# hydroponics_schema.net
KiCad netlist of a schematic drawn in EAGLE
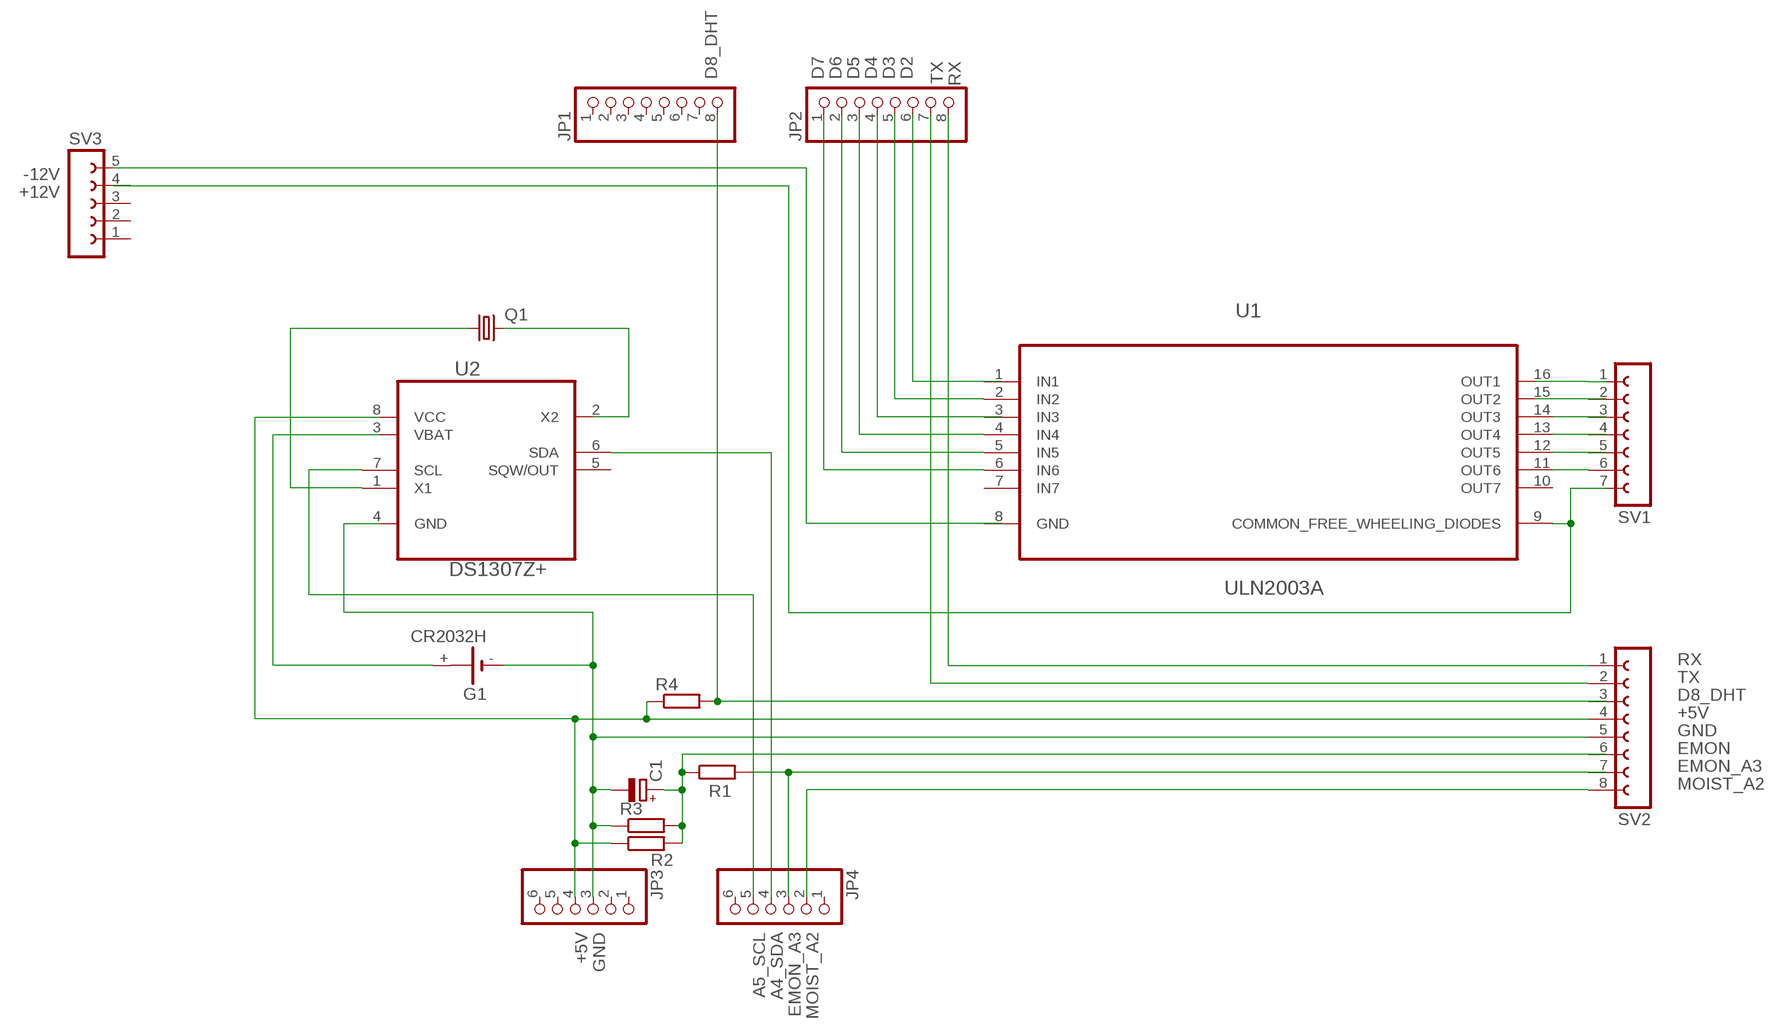
[diagram p0: schematic, sheet 1]

(export (version "E")
  (design (tool "Eeschema 10.0.6"))
  (components
    (comp (ref "C1")
      (value "CPOL-EUE2.5-6")
      (footprint "eagle-import:E2,5-6")
      (libsource (lib "eagle-import") (part "CPOL-EUE2.5-6"))
    )
    (comp (ref "G1")
      (value "CR2032H")
      (footprint "eagle-import:CR2032H")
      (libsource (lib "eagle-import") (part "CR2032H"))
    )
    (comp (ref "JP1")
      (value "PINHD-1X8/90")
      (footprint "eagle-import:1X08_90")
      (libsource (lib "eagle-import") (part "PINHD-1X8/90"))
    )
    (comp (ref "JP2")
      (value "PINHD-1X8/90")
      (footprint "eagle-import:1X08_90")
      (libsource (lib "eagle-import") (part "PINHD-1X8/90"))
    )
    (comp (ref "JP3")
      (value "PINHD-1X6/90")
      (footprint "eagle-import:1X06_90")
      (libsource (lib "eagle-import") (part "PINHD-1X6/90"))
    )
    (comp (ref "JP4")
      (value "PINHD-1X6/90")
      (footprint "eagle-import:1X06_90")
      (libsource (lib "eagle-import") (part "PINHD-1X6/90"))
    )
    (comp (ref "Q1")
      (value "CRYSTALTC38H")
      (footprint "eagle-import:TC38H")
      (libsource (lib "eagle-import") (part "CRYSTALTC38H"))
    )
    (comp (ref "R1")
      (value "R-EU_0207/10")
      (footprint "eagle-import:0207_10")
      (libsource (lib "eagle-import") (part "R-EU_0207/10"))
    )
    (comp (ref "R2")
      (value "R-EU_0207/10")
      (footprint "eagle-import:0207_10")
      (libsource (lib "eagle-import") (part "R-EU_0207/10"))
    )
    (comp (ref "R3")
      (value "R-EU_0207/10")
      (footprint "eagle-import:0207_10")
      (libsource (lib "eagle-import") (part "R-EU_0207/10"))
    )
    (comp (ref "R4")
      (value "R-EU_0207/10")
      (footprint "eagle-import:0207_10")
      (libsource (lib "eagle-import") (part "R-EU_0207/10"))
    )
    (comp (ref "SV1")
      (value "FE07-1")
      (footprint "eagle-import:FE07")
      (libsource (lib "eagle-import") (part "FE07-1"))
    )
    (comp (ref "SV2")
      (value "FE08-1")
      (footprint "eagle-import:FE08")
      (libsource (lib "eagle-import") (part "FE08-1"))
    )
    (comp (ref "SV3")
      (value "FE05-1")
      (footprint "eagle-import:FE05-1")
      (libsource (lib "eagle-import") (part "FE05-1"))
    )
    (comp (ref "U1")
      (value "ULN2003A")
      (footprint "eagle-import:DIP254P762X508-16")
      (fields (field (name "MF") "Arrow Electronics"))
      (libsource (lib "eagle-import") (part "ULN2003A"))
    )
    (comp (ref "U2")
      (value "DS1307Z+")
      (footprint "eagle-import:SOIC127P600X175-8N")
      (fields (field (name "MF") "DALLAS SEMICONDUCTOR"))
      (libsource (lib "eagle-import") (part "DS1307Z+"))
    )
  )
  (nets
    (net (code "1") (name "/+5V") (class "Default")
      (node (ref "JP3") (pin "4") (pinfunction "4_4") (pintype "passive"))
      (node (ref "R2") (pin "1") (pinfunction "1_1") (pintype "passive"))
      (node (ref "R4") (pin "1") (pinfunction "1_1") (pintype "passive"))
      (node (ref "SV2") (pin "4") (pinfunction "4_4") (pintype "passive"))
    )
    (net (code "2") (name "/+12V") (class "Default")
      (node (ref "U1") (pin "9") (pinfunction "COMMON_FREE_WHEELING_DIODES_9") (pintype "passive"))
    )
    (net (code "4") (name "/A4_SDA") (class "Default")
      (node (ref "JP4") (pin "4") (pinfunction "4_4") (pintype "passive"))
      (node (ref "U2") (pin "6") (pinfunction "SDA_6") (pintype "bidirectional"))
    )
    (net (code "5") (name "/A5_SCL") (class "Default")
      (node (ref "JP4") (pin "5") (pinfunction "5_5") (pintype "passive"))
      (node (ref "U2") (pin "7") (pinfunction "SCL_7") (pintype "input"))
    )
    (net (code "6") (name "/D2") (class "Default")
      (node (ref "JP2") (pin "6") (pinfunction "6_6") (pintype "passive"))
    )
    (net (code "7") (name "/D3") (class "Default")
      (node (ref "JP2") (pin "5") (pinfunction "5_5") (pintype "passive"))
      (node (ref "U1") (pin "2") (pinfunction "IN2_2") (pintype "input"))
    )
    (net (code "8") (name "/D4") (class "Default")
      (node (ref "JP2") (pin "4") (pinfunction "4_4") (pintype "passive"))
    )
    (net (code "9") (name "/D5") (class "Default")
      (node (ref "JP2") (pin "3") (pinfunction "3_3") (pintype "passive"))
      (node (ref "U1") (pin "4") (pinfunction "IN4_4") (pintype "input"))
    )
    (net (code "10") (name "/D6") (class "Default")
      (node (ref "JP2") (pin "2") (pinfunction "2_2") (pintype "passive"))
      (node (ref "U1") (pin "5") (pinfunction "IN5_5") (pintype "input"))
    )
    (net (code "11") (name "/D7") (class "Default")
      (node (ref "JP2") (pin "1") (pinfunction "1_1") (pintype "passive"))
      (node (ref "U1") (pin "6") (pinfunction "IN6_6") (pintype "input"))
    )
    (net (code "12") (name "/D8_DHT") (class "Default")
      (node (ref "JP1") (pin "8") (pinfunction "8_8") (pintype "passive"))
      (node (ref "R4") (pin "2") (pinfunction "2_2") (pintype "passive"))
    )
    (net (code "13") (name "/EMON") (class "Default")
      (node (ref "C1") (pin "+") (pinfunction "+_+") (pintype "passive"))
      (node (ref "R1") (pin "1") (pinfunction "1_1") (pintype "passive"))
      (node (ref "R2") (pin "2") (pinfunction "2_2") (pintype "passive"))
      (node (ref "R3") (pin "2") (pinfunction "2_2") (pintype "passive"))
    )
    (net (code "14") (name "/EMON_A3") (class "Default")
      (node (ref "JP4") (pin "3") (pinfunction "3_3") (pintype "passive"))
      (node (ref "R1") (pin "2") (pinfunction "2_2") (pintype "passive"))
    )
    (net (code "15") (name "/GND") (class "Default")
      (node (ref "C1") (pin "-") (pinfunction "-_-") (pintype "passive"))
      (node (ref "G1") (pin "-") (pinfunction "-_-") (pintype "passive"))
      (node (ref "JP3") (pin "3") (pinfunction "3_3") (pintype "passive"))
      (node (ref "R3") (pin "1") (pinfunction "1_1") (pintype "passive"))
      (node (ref "SV2") (pin "5") (pinfunction "5_5") (pintype "passive"))
    )
    (net (code "16") (name "/MOIST_A2") (class "Default")
      (node (ref "JP4") (pin "2") (pinfunction "2_2") (pintype "passive"))
      (node (ref "SV2") (pin "8") (pinfunction "8_8") (pintype "passive"))
    )
    (net (code "17") (name "/RX") (class "Default")
      (node (ref "JP2") (pin "8") (pinfunction "8_8") (pintype "passive"))
      (node (ref "SV2") (pin "1") (pinfunction "1_1") (pintype "passive"))
    )
    (net (code "18") (name "/TX") (class "Default")
      (node (ref "JP2") (pin "7") (pinfunction "7_7") (pintype "passive"))
      (node (ref "SV2") (pin "2") (pinfunction "2_2") (pintype "passive"))
    )
    (net (code "19") (name "/VCC") (class "Default")
      (node (ref "U2") (pin "8") (pinfunction "VCC_8") (pintype "power_in"))
    )
    (net (code "20") (name "Net-(U1-OUT6)") (class "Default")
      (node (ref "SV1") (pin "6") (pinfunction "6_6") (pintype "passive"))
      (node (ref "U1") (pin "11") (pinfunction "OUT6_11") (pintype "output"))
    )
    (net (code "21") (name "Net-(U2-X1)") (class "Default")
      (node (ref "Q1") (pin "1") (pinfunction "1_1") (pintype "passive"))
      (node (ref "U2") (pin "1") (pinfunction "X1_1") (pintype "input"))
    )
    (net (code "22") (name "unconnected-(G1-+-Pad+@1)") (class "Default")
      (node (ref "G1") (pin "+@1") (pinfunction "+_+@1") (pintype "passive"))
    )
    (net (code "23") (name "unconnected-(G1-Pad+)") (class "Default")
      (node (ref "G1") (pin "+") (pinfunction "+_+") (pintype "passive"))
    )
    (net (code "24") (name "unconnected-(JP1-Pad1)") (class "Default")
      (node (ref "JP1") (pin "1") (pinfunction "1_1") (pintype "passive"))
    )
    (net (code "25") (name "unconnected-(JP1-Pad2)") (class "Default")
      (node (ref "JP1") (pin "2") (pinfunction "2_2") (pintype "passive"))
    )
    (net (code "26") (name "unconnected-(JP1-Pad3)") (class "Default")
      (node (ref "JP1") (pin "3") (pinfunction "3_3") (pintype "passive"))
    )
    (net (code "27") (name "unconnected-(JP1-Pad4)") (class "Default")
      (node (ref "JP1") (pin "4") (pinfunction "4_4") (pintype "passive"))
    )
    (net (code "28") (name "unconnected-(JP1-Pad5)") (class "Default")
      (node (ref "JP1") (pin "5") (pinfunction "5_5") (pintype "passive"))
    )
    (net (code "29") (name "unconnected-(JP1-Pad6)") (class "Default")
      (node (ref "JP1") (pin "6") (pinfunction "6_6") (pintype "passive"))
    )
    (net (code "30") (name "unconnected-(JP1-Pad7)") (class "Default")
      (node (ref "JP1") (pin "7") (pinfunction "7_7") (pintype "passive"))
    )
    (net (code "31") (name "unconnected-(JP3-Pad1)") (class "Default")
      (node (ref "JP3") (pin "1") (pinfunction "1_1") (pintype "passive"))
    )
    (net (code "32") (name "unconnected-(JP3-Pad2)") (class "Default")
      (node (ref "JP3") (pin "2") (pinfunction "2_2") (pintype "passive"))
    )
    (net (code "33") (name "unconnected-(JP3-Pad5)") (class "Default")
      (node (ref "JP3") (pin "5") (pinfunction "5_5") (pintype "passive"))
    )
    (net (code "34") (name "unconnected-(JP3-Pad6)") (class "Default")
      (node (ref "JP3") (pin "6") (pinfunction "6_6") (pintype "passive"))
    )
    (net (code "35") (name "unconnected-(JP4-Pad1)") (class "Default")
      (node (ref "JP4") (pin "1") (pinfunction "1_1") (pintype "passive"))
    )
    (net (code "36") (name "unconnected-(JP4-Pad6)") (class "Default")
      (node (ref "JP4") (pin "6") (pinfunction "6_6") (pintype "passive"))
    )
    (net (code "37") (name "unconnected-(Q1-Pad2)") (class "Default")
      (node (ref "Q1") (pin "2") (pinfunction "2_2") (pintype "passive"))
    )
    (net (code "38") (name "unconnected-(SV1-Pad1)") (class "Default")
      (node (ref "SV1") (pin "1") (pinfunction "1_1") (pintype "passive"))
    )
    (net (code "39") (name "unconnected-(SV1-Pad2)") (class "Default")
      (node (ref "SV1") (pin "2") (pinfunction "2_2") (pintype "passive"))
    )
    (net (code "40") (name "unconnected-(SV1-Pad3)") (class "Default")
      (node (ref "SV1") (pin "3") (pinfunction "3_3") (pintype "passive"))
    )
    (net (code "41") (name "unconnected-(SV1-Pad4)") (class "Default")
      (node (ref "SV1") (pin "4") (pinfunction "4_4") (pintype "passive"))
    )
    (net (code "42") (name "unconnected-(SV1-Pad5)") (class "Default")
      (node (ref "SV1") (pin "5") (pinfunction "5_5") (pintype "passive"))
    )
    (net (code "43") (name "unconnected-(SV1-Pad7)") (class "Default")
      (node (ref "SV1") (pin "7") (pinfunction "7_7") (pintype "passive"))
    )
    (net (code "44") (name "unconnected-(SV2-Pad3)") (class "Default")
      (node (ref "SV2") (pin "3") (pinfunction "3_3") (pintype "passive"))
    )
    (net (code "45") (name "unconnected-(SV2-Pad6)") (class "Default")
      (node (ref "SV2") (pin "6") (pinfunction "6_6") (pintype "passive"))
    )
    (net (code "46") (name "unconnected-(SV2-Pad7)") (class "Default")
      (node (ref "SV2") (pin "7") (pinfunction "7_7") (pintype "passive"))
    )
    (net (code "47") (name "unconnected-(SV3-Pad1)") (class "Default")
      (node (ref "SV3") (pin "1") (pinfunction "1_1") (pintype "passive"))
    )
    (net (code "48") (name "unconnected-(SV3-Pad2)") (class "Default")
      (node (ref "SV3") (pin "2") (pinfunction "2_2") (pintype "passive"))
    )
    (net (code "49") (name "unconnected-(SV3-Pad3)") (class "Default")
      (node (ref "SV3") (pin "3") (pinfunction "3_3") (pintype "passive"))
    )
    (net (code "50") (name "unconnected-(SV3-Pad4)") (class "Default")
      (node (ref "SV3") (pin "4") (pinfunction "4_4") (pintype "passive"))
    )
    (net (code "51") (name "unconnected-(SV3-Pad5)") (class "Default")
      (node (ref "SV3") (pin "5") (pinfunction "5_5") (pintype "passive"))
    )
    (net (code "52") (name "unconnected-(U1-GND-Pad8)") (class "Default")
      (node (ref "U1") (pin "8") (pinfunction "GND_8") (pintype "passive"))
    )
    (net (code "53") (name "unconnected-(U1-IN1-Pad1)") (class "Default")
      (node (ref "U1") (pin "1") (pinfunction "IN1_1") (pintype "input"))
    )
    (net (code "54") (name "unconnected-(U1-IN3-Pad3)") (class "Default")
      (node (ref "U1") (pin "3") (pinfunction "IN3_3") (pintype "input"))
    )
    (net (code "55") (name "unconnected-(U1-IN7-Pad7)") (class "Default")
      (node (ref "U1") (pin "7") (pinfunction "IN7_7") (pintype "input"))
    )
    (net (code "56") (name "unconnected-(U1-OUT1-Pad16)") (class "Default")
      (node (ref "U1") (pin "16") (pinfunction "OUT1_16") (pintype "output"))
    )
    (net (code "57") (name "unconnected-(U1-OUT2-Pad15)") (class "Default")
      (node (ref "U1") (pin "15") (pinfunction "OUT2_15") (pintype "output"))
    )
    (net (code "58") (name "unconnected-(U1-OUT3-Pad14)") (class "Default")
      (node (ref "U1") (pin "14") (pinfunction "OUT3_14") (pintype "output"))
    )
    (net (code "59") (name "unconnected-(U1-OUT4-Pad13)") (class "Default")
      (node (ref "U1") (pin "13") (pinfunction "OUT4_13") (pintype "output"))
    )
    (net (code "60") (name "unconnected-(U1-OUT5-Pad12)") (class "Default")
      (node (ref "U1") (pin "12") (pinfunction "OUT5_12") (pintype "output"))
    )
    (net (code "61") (name "unconnected-(U1-OUT7-Pad10)") (class "Default")
      (node (ref "U1") (pin "10") (pinfunction "OUT7_10") (pintype "output"))
    )
    (net (code "62") (name "unconnected-(U2-GND-Pad4)") (class "Default")
      (node (ref "U2") (pin "4") (pinfunction "GND_4") (pintype "passive"))
    )
    (net (code "63") (name "unconnected-(U2-SQW{slash}OUT-Pad5)") (class "Default")
      (node (ref "U2") (pin "5") (pinfunction "SQW/OUT_5") (pintype "bidirectional"))
    )
    (net (code "64") (name "unconnected-(U2-VBAT-Pad3)") (class "Default")
      (node (ref "U2") (pin "3") (pinfunction "VBAT_3") (pintype "input"))
    )
    (net (code "65") (name "unconnected-(U2-X2-Pad2)") (class "Default")
      (node (ref "U2") (pin "2") (pinfunction "X2_2") (pintype "output"))
    )
  )
)
